# POL_JFET.net
KiCad netlist of a schematic drawn in Altium Designer
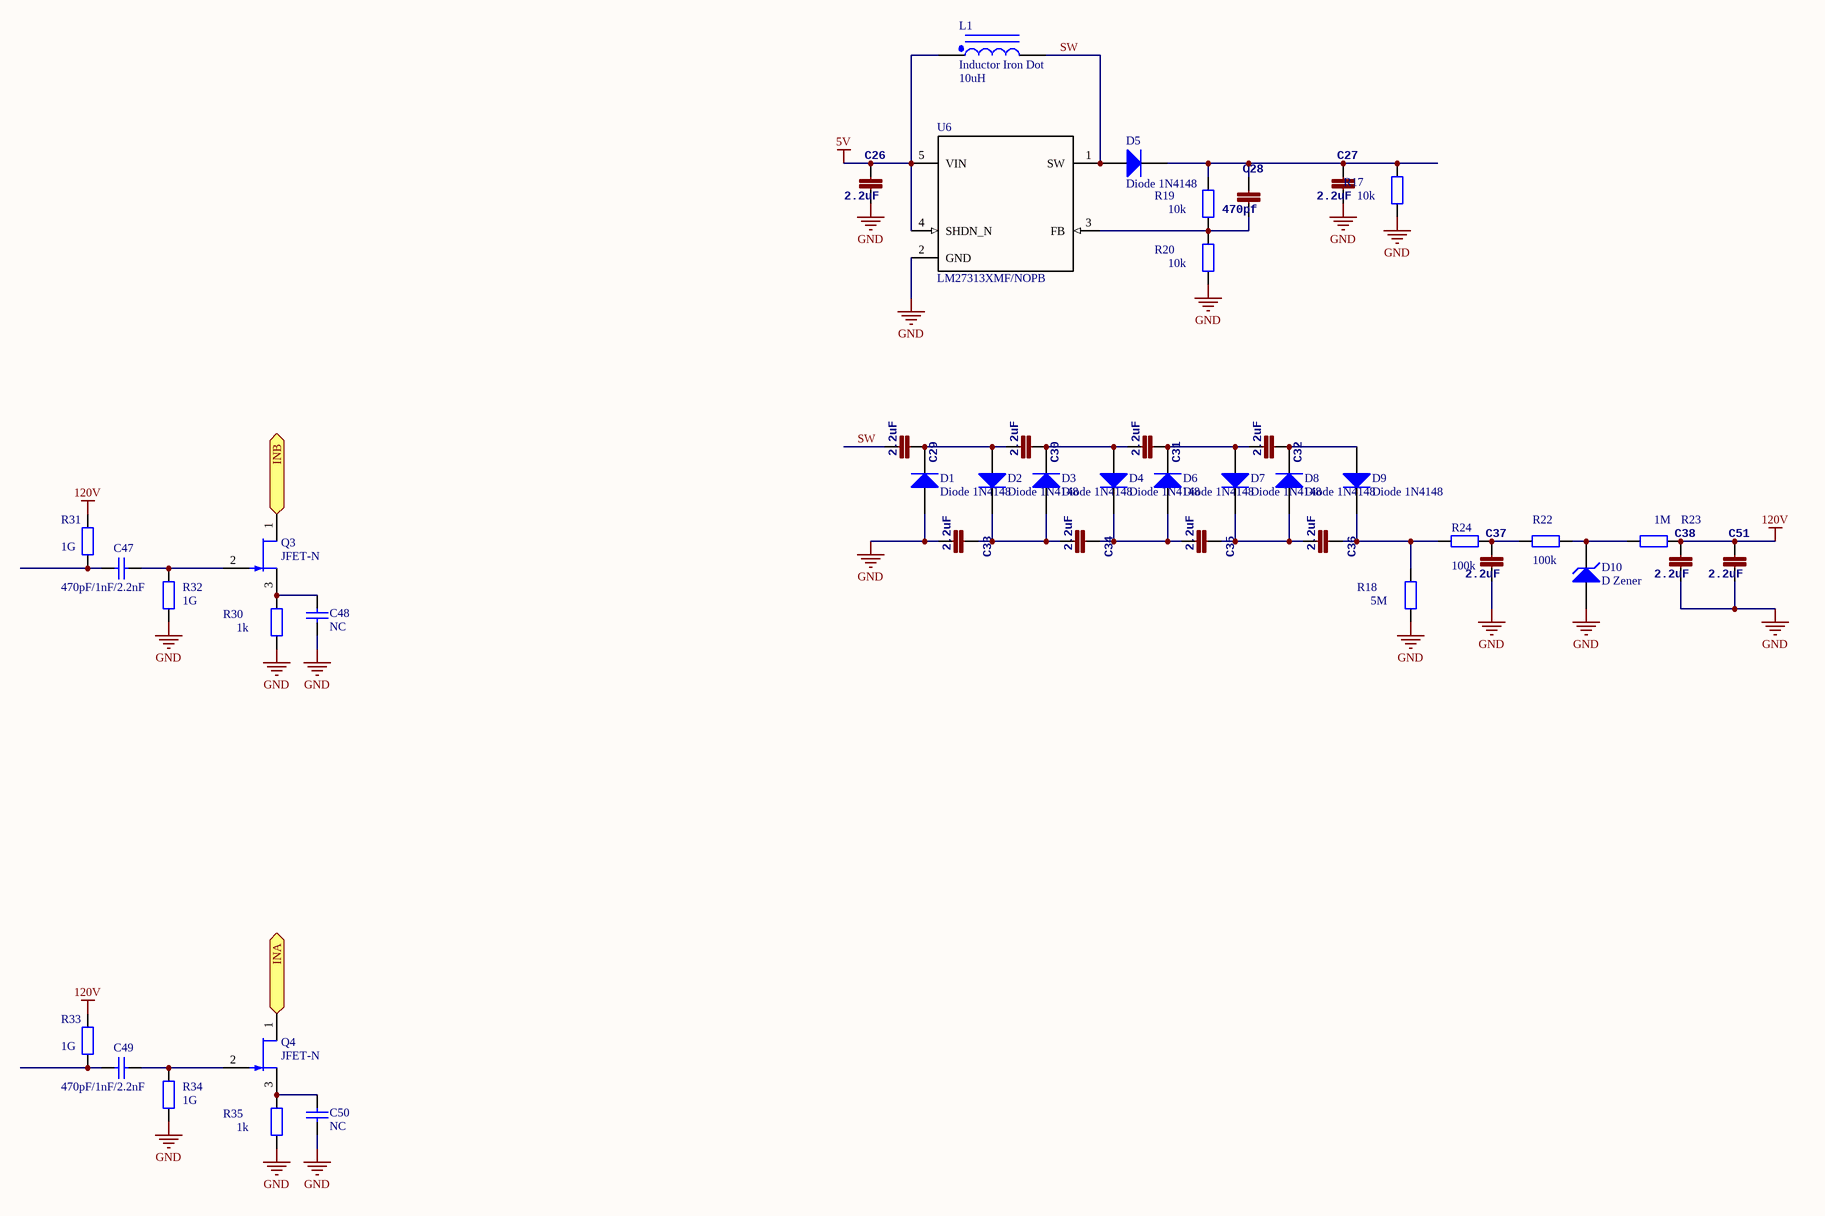
[diagram p0: POL&JFET.SchDoc]

(export (version "E")
  (design (tool "Eeschema 10.0.6"))
  (components
    (comp (ref "C26")
      (value "2.2uF")
      (footprint "0805")
      (description "<b>Capacitor</b>\nStandard 0603 ceramic capacitor, and 0.1\" leaded capacitor.")
      (fields (field (name "PARTNO") "CC0402ZRY5V7BB104"))
      (libsource (lib "") (part "CAP0402-CAP_1"))
    )
    (comp (ref "C27")
      (value "2.2uF")
      (footprint "0805")
      (description "<b>Capacitor</b>\nStandard 0603 ceramic capacitor, and 0.1\" leaded capacitor.")
      (fields (field (name "PARTNO") "CC0402ZRY5V7BB104"))
      (libsource (lib "") (part "CAP0402-CAP_1"))
    )
    (comp (ref "C28")
      (value "470pf")
      (footprint "0402")
      (description "<b>Capacitor</b>\nStandard 0603 ceramic capacitor, and 0.1\" leaded capacitor.")
      (fields (field (name "PARTNO") "CC0402ZRY5V7BB104"))
      (libsource (lib "") (part "CAP0402-CAP_1"))
    )
    (comp (ref "C29")
      (value "2.2uF")
      (footprint "0805")
      (description "<b>Capacitor</b>\nStandard 0603 ceramic capacitor, and 0.1\" leaded capacitor.")
      (fields (field (name "PARTNO") "CC0402ZRY5V7BB104"))
      (libsource (lib "pixhawk2") (part "CAP0402-CAP"))
    )
    (comp (ref "C30")
      (value "2.2uF")
      (footprint "0805")
      (description "<b>Capacitor</b>\nStandard 0603 ceramic capacitor, and 0.1\" leaded capacitor.")
      (fields (field (name "PARTNO") "CC0402ZRY5V7BB104"))
      (libsource (lib "pixhawk2") (part "CAP0402-CAP"))
    )
    (comp (ref "C31")
      (value "2.2uF")
      (footprint "0805")
      (description "<b>Capacitor</b>\nStandard 0603 ceramic capacitor, and 0.1\" leaded capacitor.")
      (fields (field (name "PARTNO") "CC0402ZRY5V7BB104"))
      (libsource (lib "pixhawk2") (part "CAP0402-CAP"))
    )
    (comp (ref "C32")
      (value "2.2uF")
      (footprint "0805")
      (description "<b>Capacitor</b>\nStandard 0603 ceramic capacitor, and 0.1\" leaded capacitor.")
      (fields (field (name "PARTNO") "CC0402ZRY5V7BB104"))
      (libsource (lib "pixhawk2") (part "CAP0402-CAP"))
    )
    (comp (ref "C33")
      (value "2.2uF")
      (footprint "0805")
      (description "<b>Capacitor</b>\nStandard 0603 ceramic capacitor, and 0.1\" leaded capacitor.")
      (fields (field (name "PARTNO") "CC0402ZRY5V7BB104"))
      (libsource (lib "pixhawk2") (part "CAP0402-CAP"))
    )
    (comp (ref "C34")
      (value "2.2uF")
      (footprint "0805")
      (description "<b>Capacitor</b>\nStandard 0603 ceramic capacitor, and 0.1\" leaded capacitor.")
      (fields (field (name "PARTNO") "CC0402ZRY5V7BB104"))
      (libsource (lib "pixhawk2") (part "CAP0402-CAP"))
    )
    (comp (ref "C35")
      (value "2.2uF")
      (footprint "0805")
      (description "<b>Capacitor</b>\nStandard 0603 ceramic capacitor, and 0.1\" leaded capacitor.")
      (fields (field (name "PARTNO") "CC0402ZRY5V7BB104"))
      (libsource (lib "pixhawk2") (part "CAP0402-CAP"))
    )
    (comp (ref "C36")
      (value "2.2uF")
      (footprint "0805")
      (description "<b>Capacitor</b>\nStandard 0603 ceramic capacitor, and 0.1\" leaded capacitor.")
      (fields (field (name "PARTNO") "CC0402ZRY5V7BB104"))
      (libsource (lib "pixhawk2") (part "CAP0402-CAP"))
    )
    (comp (ref "C37")
      (value "2.2uF")
      (footprint "0805")
      (description "<b>Capacitor</b>\nStandard 0603 ceramic capacitor, and 0.1\" leaded capacitor.")
      (fields (field (name "PARTNO") "CC0402ZRY5V7BB104"))
      (libsource (lib "") (part "CAP0402-CAP_1"))
    )
    (comp (ref "C38")
      (value "2.2uF")
      (footprint "0805")
      (description "<b>Capacitor</b>\nStandard 0603 ceramic capacitor, and 0.1\" leaded capacitor.")
      (fields (field (name "PARTNO") "CC0402ZRY5V7BB104"))
      (libsource (lib "") (part "CAP0402-CAP_1"))
    )
    (comp (ref "C47")
      (value "470pF/1nF/2.2nF")
      (footprint "CL21-5mm-1A")
      (description "Capacitor")
      (fields (field (name "PUBLISHER") "Altium Limited"))
      (libsource (lib "RTC6705") (part "Cap"))
    )
    (comp (ref "C48")
      (value "NC")
      (footprint "0402")
      (description "Capacitor")
      (fields (field (name "PUBLISHER") "Altium Limited"))
      (libsource (lib "RTC6705") (part "Cap"))
    )
    (comp (ref "C49")
      (value "470pF/1nF/2.2nF")
      (footprint "CL21-5mm-1A")
      (description "Capacitor")
      (fields (field (name "PUBLISHER") "Altium Limited"))
      (libsource (lib "RTC6705") (part "Cap"))
    )
    (comp (ref "C50")
      (value "NC")
      (footprint "0402")
      (description "Capacitor")
      (fields (field (name "PUBLISHER") "Altium Limited"))
      (libsource (lib "RTC6705") (part "Cap"))
    )
    (comp (ref "C51")
      (value "2.2uF")
      (footprint "0805")
      (description "<b>Capacitor</b>\nStandard 0603 ceramic capacitor, and 0.1\" leaded capacitor.")
      (fields (field (name "PARTNO") "CC0402ZRY5V7BB104"))
      (libsource (lib "") (part "CAP0402-CAP_1"))
    )
    (comp (ref "D1")
      (value "Diode 1N4148")
      (footprint "LC-SOD-323")
      (description "High Conductance Fast Diode")
      (fields (field (name "PUBLISHER") "Altium Limited"))
      (libsource (lib "Miscellaneous Devices") (part "Diode 1N4148"))
    )
    (comp (ref "D2")
      (value "Diode 1N4148")
      (footprint "LC-SOD-323")
      (description "High Conductance Fast Diode")
      (fields (field (name "PUBLISHER") "Altium Limited"))
      (libsource (lib "Miscellaneous Devices") (part "Diode 1N4148"))
    )
    (comp (ref "D3")
      (value "Diode 1N4148")
      (footprint "LC-SOD-323")
      (description "High Conductance Fast Diode")
      (fields (field (name "PUBLISHER") "Altium Limited"))
      (libsource (lib "Miscellaneous Devices") (part "Diode 1N4148"))
    )
    (comp (ref "D4")
      (value "Diode 1N4148")
      (footprint "LC-SOD-323")
      (description "High Conductance Fast Diode")
      (fields (field (name "PUBLISHER") "Altium Limited"))
      (libsource (lib "Miscellaneous Devices") (part "Diode 1N4148"))
    )
    (comp (ref "D5")
      (value "Diode 1N4148")
      (footprint "LC-SOD-323")
      (description "High Conductance Fast Diode")
      (fields (field (name "PUBLISHER") "Altium Limited"))
      (libsource (lib "Miscellaneous Devices") (part "Diode 1N4148"))
    )
    (comp (ref "D6")
      (value "Diode 1N4148")
      (footprint "LC-SOD-323")
      (description "High Conductance Fast Diode")
      (fields (field (name "PUBLISHER") "Altium Limited"))
      (libsource (lib "Miscellaneous Devices") (part "Diode 1N4148"))
    )
    (comp (ref "D7")
      (value "Diode 1N4148")
      (footprint "LC-SOD-323")
      (description "High Conductance Fast Diode")
      (fields (field (name "PUBLISHER") "Altium Limited"))
      (libsource (lib "Miscellaneous Devices") (part "Diode 1N4148"))
    )
    (comp (ref "D8")
      (value "Diode 1N4148")
      (footprint "LC-SOD-323")
      (description "High Conductance Fast Diode")
      (fields (field (name "PUBLISHER") "Altium Limited"))
      (libsource (lib "Miscellaneous Devices") (part "Diode 1N4148"))
    )
    (comp (ref "D9")
      (value "Diode 1N4148")
      (footprint "LC-SOD-323")
      (description "High Conductance Fast Diode")
      (fields (field (name "PUBLISHER") "Altium Limited"))
      (libsource (lib "Miscellaneous Devices") (part "Diode 1N4148"))
    )
    (comp (ref "D10")
      (value "D Zener")
      (footprint "LC-SOT-323(SC-70):SMA")
      (description "Zener Diode")
      (fields (field (name "PUBLISHER") "Altium Limited"))
      (libsource (lib "Miscellaneous Devices") (part "D Zener"))
    )
    (comp (ref "L1")
      (value "Inductor Iron Dot")
      (footprint "L4015")
      (description "Magnetic-Core Inductor with Winding Polarity Marking")
      (fields (field (name "ALTIUM_VALUE") "10uH") (field (name "PUBLISHER") "Altium Limited"))
      (libsource (lib "Miscellaneous Devices") (part "Inductor Iron Dot"))
    )
    (comp (ref "Q3")
      (value "JFET-N")
      (footprint "TO-92")
      (description "N-Channel JFET")
      (fields (field (name "PUBLISHER") "Altium Limited"))
      (libsource (lib "Miscellaneous Devices") (part "JFET-N"))
    )
    (comp (ref "Q4")
      (value "JFET-N")
      (footprint "TO-92")
      (description "N-Channel JFET")
      (fields (field (name "PUBLISHER") "Altium Limited"))
      (libsource (lib "Miscellaneous Devices") (part "JFET-N"))
    )
    (comp (ref "R17")
      (value "10k")
      (footprint "0402")
      (description "Resistor")
      (fields (field (name "PUBLISHER") "Altium Limited"))
      (libsource (lib "Miscellaneous Devices") (part "Res2"))
    )
    (comp (ref "R18")
      (value "5M")
      (footprint "0402")
      (description "Resistor")
      (fields (field (name "PUBLISHER") "Altium Limited"))
      (libsource (lib "Miscellaneous Devices") (part "Res2"))
    )
    (comp (ref "R19")
      (value "10k")
      (footprint "0402")
      (description "Resistor")
      (fields (field (name "PUBLISHER") "Altium Limited"))
      (libsource (lib "Miscellaneous Devices") (part "Res2"))
    )
    (comp (ref "R20")
      (value "10k")
      (footprint "0402")
      (description "Resistor")
      (fields (field (name "PUBLISHER") "Altium Limited"))
      (libsource (lib "Miscellaneous Devices") (part "Res2"))
    )
    (comp (ref "R22")
      (value "100k")
      (footprint "0402")
      (description "Resistor")
      (fields (field (name "PUBLISHER") "Altium Limited"))
      (libsource (lib "") (part "Res2_1"))
    )
    (comp (ref "R23")
      (value "1M")
      (footprint "0402")
      (description "Resistor")
      (fields (field (name "PUBLISHER") "Altium Limited"))
      (libsource (lib "") (part "Res2_1"))
    )
    (comp (ref "R24")
      (value "100k")
      (footprint "0402")
      (description "Resistor")
      (fields (field (name "PUBLISHER") "Altium Limited"))
      (libsource (lib "") (part "Res2_1"))
    )
    (comp (ref "R30")
      (value "1k")
      (footprint "0402")
      (description "Resistor")
      (fields (field (name "PUBLISHER") "Altium Limited"))
      (libsource (lib "Miscellaneous Devices") (part "Res2"))
    )
    (comp (ref "R31")
      (value "1G")
      (footprint "R-1G")
      (description "Resistor")
      (fields (field (name "PUBLISHER") "Altium Limited"))
      (libsource (lib "Miscellaneous Devices") (part "Res2"))
    )
    (comp (ref "R32")
      (value "1G")
      (footprint "R-1G")
      (description "Resistor")
      (fields (field (name "PUBLISHER") "Altium Limited"))
      (libsource (lib "Miscellaneous Devices") (part "Res2"))
    )
    (comp (ref "R33")
      (value "1G")
      (footprint "R-1G")
      (description "Resistor")
      (fields (field (name "PUBLISHER") "Altium Limited"))
      (libsource (lib "Miscellaneous Devices") (part "Res2"))
    )
    (comp (ref "R34")
      (value "1G")
      (footprint "R-1G")
      (description "Resistor")
      (fields (field (name "PUBLISHER") "Altium Limited"))
      (libsource (lib "Miscellaneous Devices") (part "Res2"))
    )
    (comp (ref "R35")
      (value "1k")
      (footprint "0402")
      (description "Resistor")
      (fields (field (name "PUBLISHER") "Altium Limited"))
      (libsource (lib "Miscellaneous Devices") (part "Res2"))
    )
    (comp (ref "U6")
      (value "LM27313XMF/NOPB")
      (footprint "SOT23-5")
      (description "Imported")
      (fields (field (name "MANUFACTURER") "Texas Instruments"))
      (libsource (lib "complements") (part "LM27313XMF/NOPB"))
    )
  )
  (nets
    (net (code "1") (name "/INA") (class "Default")
      (node (ref "Q4") (pin "1") (pinfunction "D_1") (pintype "passive"))
    )
    (net (code "2") (name "/INB") (class "Default")
      (node (ref "Q3") (pin "1") (pinfunction "D_1") (pintype "passive"))
    )
    (net (code "3") (name "/SW") (class "Default")
      (node (ref "C29") (pin "1") (pinfunction "1_1") (pintype "passive"))
      (node (ref "D5") (pin "1") (pinfunction "A_1") (pintype "passive"))
      (node (ref "L1") (pin "2") (pinfunction "2_2") (pintype "passive"))
      (node (ref "U6") (pin "1") (pinfunction "SW_1") (pintype "power_in"))
    )
    (net (code "4") (name "5V") (class "Default")
      (node (ref "C26") (pin "2") (pinfunction "2_2") (pintype "passive"))
      (node (ref "L1") (pin "1") (pinfunction "1_1") (pintype "passive"))
      (node (ref "U6") (pin "4") (pinfunction "SHDN_N_4") (pintype "input"))
      (node (ref "U6") (pin "5") (pinfunction "VIN_5") (pintype "power_in"))
    )
    (net (code "5") (name "120V") (class "Default")
      (node (ref "C38") (pin "2") (pinfunction "2_2") (pintype "passive"))
      (node (ref "C51") (pin "2") (pinfunction "2_2") (pintype "passive"))
      (node (ref "R23") (pin "1") (pinfunction "1_1") (pintype "passive"))
      (node (ref "R31") (pin "2") (pinfunction "2_2") (pintype "passive"))
      (node (ref "R33") (pin "2") (pinfunction "2_2") (pintype "passive"))
    )
    (net (code "6") (name "GND") (class "Default")
      (node (ref "C26") (pin "1") (pinfunction "1_1") (pintype "passive"))
      (node (ref "C27") (pin "1") (pinfunction "1_1") (pintype "passive"))
      (node (ref "C33") (pin "1") (pinfunction "1_1") (pintype "passive"))
      (node (ref "C37") (pin "1") (pinfunction "1_1") (pintype "passive"))
      (node (ref "C38") (pin "1") (pinfunction "1_1") (pintype "passive"))
      (node (ref "C48") (pin "2") (pinfunction "2_2") (pintype "passive"))
      (node (ref "C50") (pin "2") (pinfunction "2_2") (pintype "passive"))
      (node (ref "C51") (pin "1") (pinfunction "1_1") (pintype "passive"))
      (node (ref "D1") (pin "1") (pinfunction "A_1") (pintype "passive"))
      (node (ref "D10") (pin "1") (pinfunction "A_1") (pintype "passive"))
      (node (ref "R17") (pin "1") (pinfunction "1_1") (pintype "passive"))
      (node (ref "R18") (pin "1") (pinfunction "1_1") (pintype "passive"))
      (node (ref "R20") (pin "1") (pinfunction "1_1") (pintype "passive"))
      (node (ref "R30") (pin "1") (pinfunction "1_1") (pintype "passive"))
      (node (ref "R32") (pin "1") (pinfunction "1_1") (pintype "passive"))
      (node (ref "R34") (pin "1") (pinfunction "1_1") (pintype "passive"))
      (node (ref "R35") (pin "1") (pinfunction "1_1") (pintype "passive"))
      (node (ref "U6") (pin "2") (pinfunction "GND_2") (pintype "power_in"))
    )
    (net (code "7") (name "Net-(C37-Pad2)") (class "Default")
      (node (ref "C37") (pin "2") (pinfunction "2_2") (pintype "passive"))
      (node (ref "R22") (pin "2") (pinfunction "2_2") (pintype "passive"))
      (node (ref "R24") (pin "1") (pinfunction "1_1") (pintype "passive"))
    )
    (net (code "8") (name "Net-(C47-Pad1)") (class "Default")
      (node (ref "C47") (pin "1") (pinfunction "1_1") (pintype "passive"))
      (node (ref "R31") (pin "1") (pinfunction "1_1") (pintype "passive"))
    )
    (net (code "9") (name "Net-(C49-Pad1)") (class "Default")
      (node (ref "C49") (pin "1") (pinfunction "1_1") (pintype "passive"))
      (node (ref "R33") (pin "1") (pinfunction "1_1") (pintype "passive"))
    )
    (net (code "10") (name "Net-(D1-K)") (class "Default")
      (node (ref "C29") (pin "2") (pinfunction "2_2") (pintype "passive"))
      (node (ref "C30") (pin "1") (pinfunction "1_1") (pintype "passive"))
      (node (ref "D1") (pin "2") (pinfunction "K_2") (pintype "passive"))
      (node (ref "D2") (pin "1") (pinfunction "A_1") (pintype "passive"))
    )
    (net (code "11") (name "Net-(D2-K)") (class "Default")
      (node (ref "C33") (pin "2") (pinfunction "2_2") (pintype "passive"))
      (node (ref "C34") (pin "1") (pinfunction "1_1") (pintype "passive"))
      (node (ref "D2") (pin "2") (pinfunction "K_2") (pintype "passive"))
      (node (ref "D3") (pin "1") (pinfunction "A_1") (pintype "passive"))
    )
    (net (code "12") (name "Net-(D3-K)") (class "Default")
      (node (ref "C30") (pin "2") (pinfunction "2_2") (pintype "passive"))
      (node (ref "C31") (pin "1") (pinfunction "1_1") (pintype "passive"))
      (node (ref "D3") (pin "2") (pinfunction "K_2") (pintype "passive"))
      (node (ref "D4") (pin "1") (pinfunction "A_1") (pintype "passive"))
    )
    (net (code "13") (name "Net-(D4-K)") (class "Default")
      (node (ref "C34") (pin "2") (pinfunction "2_2") (pintype "passive"))
      (node (ref "C35") (pin "1") (pinfunction "1_1") (pintype "passive"))
      (node (ref "D4") (pin "2") (pinfunction "K_2") (pintype "passive"))
      (node (ref "D6") (pin "1") (pinfunction "A_1") (pintype "passive"))
    )
    (net (code "14") (name "Net-(D5-K)") (class "Default")
      (node (ref "C27") (pin "2") (pinfunction "2_2") (pintype "passive"))
      (node (ref "C28") (pin "2") (pinfunction "2_2") (pintype "passive"))
      (node (ref "D5") (pin "2") (pinfunction "K_2") (pintype "passive"))
      (node (ref "R17") (pin "2") (pinfunction "2_2") (pintype "passive"))
      (node (ref "R19") (pin "2") (pinfunction "2_2") (pintype "passive"))
    )
    (net (code "15") (name "Net-(D6-K)") (class "Default")
      (node (ref "C31") (pin "2") (pinfunction "2_2") (pintype "passive"))
      (node (ref "C32") (pin "1") (pinfunction "1_1") (pintype "passive"))
      (node (ref "D6") (pin "2") (pinfunction "K_2") (pintype "passive"))
      (node (ref "D7") (pin "1") (pinfunction "A_1") (pintype "passive"))
    )
    (net (code "16") (name "Net-(D7-K)") (class "Default")
      (node (ref "C35") (pin "2") (pinfunction "2_2") (pintype "passive"))
      (node (ref "C36") (pin "1") (pinfunction "1_1") (pintype "passive"))
      (node (ref "D7") (pin "2") (pinfunction "K_2") (pintype "passive"))
      (node (ref "D8") (pin "1") (pinfunction "A_1") (pintype "passive"))
    )
    (net (code "17") (name "Net-(D8-K)") (class "Default")
      (node (ref "C32") (pin "2") (pinfunction "2_2") (pintype "passive"))
      (node (ref "D8") (pin "2") (pinfunction "K_2") (pintype "passive"))
      (node (ref "D9") (pin "1") (pinfunction "A_1") (pintype "passive"))
    )
    (net (code "18") (name "Net-(D9-K)") (class "Default")
      (node (ref "C36") (pin "2") (pinfunction "2_2") (pintype "passive"))
      (node (ref "D9") (pin "2") (pinfunction "K_2") (pintype "passive"))
      (node (ref "R18") (pin "2") (pinfunction "2_2") (pintype "passive"))
      (node (ref "R24") (pin "2") (pinfunction "2_2") (pintype "passive"))
    )
    (net (code "19") (name "Net-(D10-K)") (class "Default")
      (node (ref "D10") (pin "2") (pinfunction "K_2") (pintype "passive"))
      (node (ref "R22") (pin "1") (pinfunction "1_1") (pintype "passive"))
      (node (ref "R23") (pin "2") (pinfunction "2_2") (pintype "passive"))
    )
    (net (code "20") (name "Net-(Q3-G)") (class "Default")
      (node (ref "C47") (pin "2") (pinfunction "2_2") (pintype "passive"))
      (node (ref "Q3") (pin "2") (pinfunction "G_2") (pintype "passive"))
      (node (ref "R32") (pin "2") (pinfunction "2_2") (pintype "passive"))
    )
    (net (code "21") (name "Net-(Q3-S)") (class "Default")
      (node (ref "C48") (pin "1") (pinfunction "1_1") (pintype "passive"))
      (node (ref "Q3") (pin "3") (pinfunction "S_3") (pintype "passive"))
      (node (ref "R30") (pin "2") (pinfunction "2_2") (pintype "passive"))
    )
    (net (code "22") (name "Net-(Q4-G)") (class "Default")
      (node (ref "C49") (pin "2") (pinfunction "2_2") (pintype "passive"))
      (node (ref "Q4") (pin "2") (pinfunction "G_2") (pintype "passive"))
      (node (ref "R34") (pin "2") (pinfunction "2_2") (pintype "passive"))
    )
    (net (code "23") (name "Net-(Q4-S)") (class "Default")
      (node (ref "C50") (pin "1") (pinfunction "1_1") (pintype "passive"))
      (node (ref "Q4") (pin "3") (pinfunction "S_3") (pintype "passive"))
      (node (ref "R35") (pin "2") (pinfunction "2_2") (pintype "passive"))
    )
    (net (code "24") (name "Net-(U6-FB)") (class "Default")
      (node (ref "C28") (pin "1") (pinfunction "1_1") (pintype "passive"))
      (node (ref "R19") (pin "1") (pinfunction "1_1") (pintype "passive"))
      (node (ref "R20") (pin "2") (pinfunction "2_2") (pintype "passive"))
      (node (ref "U6") (pin "3") (pinfunction "FB_3") (pintype "input"))
    )
  )
)
